# GPIO_SW.net
KiCad netlist of a schematic drawn in Altium Designer
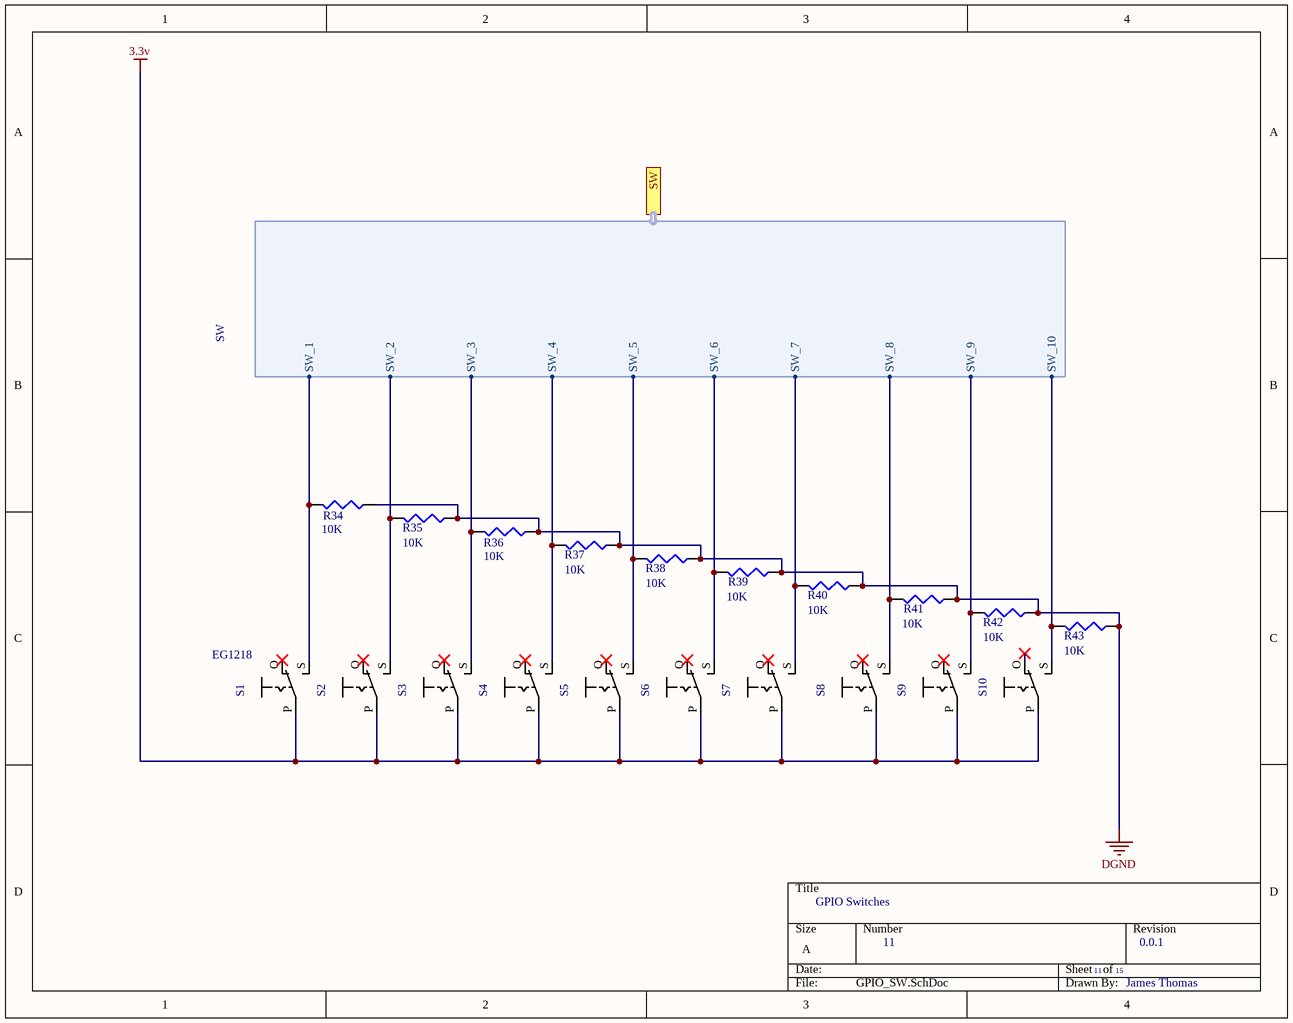
[diagram p0: GPIO_SW.SchDoc]

(export (version "E")
  (design (tool "Eeschema 10.0.6"))
  (components
    (comp (ref "R34")
      (value "10K")
      (footprint "J1-0603")
      (description "Resistor")
      (fields (field (name "Comment") "Res3") (field (name "PUBLISHER") "Altium Limited"))
      (libsource (lib "Miscellaneous Devices") (part "Res3"))
    )
    (comp (ref "R35")
      (value "10K")
      (footprint "J1-0603")
      (description "Resistor")
      (fields (field (name "Comment") "Res3") (field (name "PUBLISHER") "Altium Limited"))
      (libsource (lib "Miscellaneous Devices") (part "Res3"))
    )
    (comp (ref "R36")
      (value "10K")
      (footprint "J1-0603")
      (description "Resistor")
      (fields (field (name "Comment") "Res3") (field (name "PUBLISHER") "Altium Limited"))
      (libsource (lib "Miscellaneous Devices") (part "Res3"))
    )
    (comp (ref "R37")
      (value "10K")
      (footprint "J1-0603")
      (description "Resistor")
      (fields (field (name "Comment") "Res3") (field (name "PUBLISHER") "Altium Limited"))
      (libsource (lib "Miscellaneous Devices") (part "Res3"))
    )
    (comp (ref "R38")
      (value "10K")
      (footprint "J1-0603")
      (description "Resistor")
      (fields (field (name "Comment") "Res3") (field (name "PUBLISHER") "Altium Limited"))
      (libsource (lib "Miscellaneous Devices") (part "Res3"))
    )
    (comp (ref "R39")
      (value "10K")
      (footprint "J1-0603")
      (description "Resistor")
      (fields (field (name "Comment") "Res3") (field (name "PUBLISHER") "Altium Limited"))
      (libsource (lib "Miscellaneous Devices") (part "Res3"))
    )
    (comp (ref "R40")
      (value "10K")
      (footprint "J1-0603")
      (description "Resistor")
      (fields (field (name "Comment") "Res3") (field (name "PUBLISHER") "Altium Limited"))
      (libsource (lib "Miscellaneous Devices") (part "Res3"))
    )
    (comp (ref "R41")
      (value "10K")
      (footprint "J1-0603")
      (description "Resistor")
      (fields (field (name "Comment") "Res3") (field (name "PUBLISHER") "Altium Limited"))
      (libsource (lib "Miscellaneous Devices") (part "Res3"))
    )
    (comp (ref "R42")
      (value "10K")
      (footprint "J1-0603")
      (description "Resistor")
      (fields (field (name "Comment") "Res3") (field (name "PUBLISHER") "Altium Limited"))
      (libsource (lib "Miscellaneous Devices") (part "Res3"))
    )
    (comp (ref "R43")
      (value "10K")
      (footprint "J1-0603")
      (description "Resistor")
      (fields (field (name "Comment") "Res3") (field (name "PUBLISHER") "Altium Limited"))
      (libsource (lib "Miscellaneous Devices") (part "Res3"))
    )
    (comp (ref "S1")
      (value "EG1218")
      (footprint "*EG1218_EG1218(Primary)")
      (description "Slide Switch SPDT Through Hole")
      (fields (field (name "MF") "E-Switch") (field (name "DIGI-KEY_PART_NUMBER") "EG1903-ND"))
      (libsource (lib "Components") (part "EG1218"))
    )
    (comp (ref "S2")
      (value "EG1218")
      (footprint "*EG1218_EG1218(Primary)")
      (description "Slide Switch SPDT Through Hole")
      (fields (field (name "MF") "E-Switch") (field (name "DIGI-KEY_PART_NUMBER") "EG1903-ND"))
      (libsource (lib "Components") (part "EG1218"))
    )
    (comp (ref "S3")
      (value "EG1218")
      (footprint "*EG1218_EG1218(Primary)")
      (description "Slide Switch SPDT Through Hole")
      (fields (field (name "MF") "E-Switch") (field (name "DIGI-KEY_PART_NUMBER") "EG1903-ND"))
      (libsource (lib "Components") (part "EG1218"))
    )
    (comp (ref "S4")
      (value "EG1218")
      (footprint "*EG1218_EG1218(Primary)")
      (description "Slide Switch SPDT Through Hole")
      (fields (field (name "MF") "E-Switch") (field (name "DIGI-KEY_PART_NUMBER") "EG1903-ND"))
      (libsource (lib "Components") (part "EG1218"))
    )
    (comp (ref "S5")
      (value "EG1218")
      (footprint "*EG1218_EG1218(Primary)")
      (description "Slide Switch SPDT Through Hole")
      (fields (field (name "MF") "E-Switch") (field (name "DIGI-KEY_PART_NUMBER") "EG1903-ND"))
      (libsource (lib "Components") (part "EG1218"))
    )
    (comp (ref "S6")
      (value "EG1218")
      (footprint "*EG1218_EG1218(Primary)")
      (description "Slide Switch SPDT Through Hole")
      (fields (field (name "MF") "E-Switch") (field (name "DIGI-KEY_PART_NUMBER") "EG1903-ND"))
      (libsource (lib "Components") (part "EG1218"))
    )
    (comp (ref "S7")
      (value "EG1218")
      (footprint "*EG1218_EG1218(Primary)")
      (description "Slide Switch SPDT Through Hole")
      (fields (field (name "MF") "E-Switch") (field (name "DIGI-KEY_PART_NUMBER") "EG1903-ND"))
      (libsource (lib "Components") (part "EG1218"))
    )
    (comp (ref "S8")
      (value "EG1218")
      (footprint "*EG1218_EG1218(Primary)")
      (description "Slide Switch SPDT Through Hole")
      (fields (field (name "MF") "E-Switch") (field (name "DIGI-KEY_PART_NUMBER") "EG1903-ND"))
      (libsource (lib "Components") (part "EG1218"))
    )
    (comp (ref "S9")
      (value "EG1218")
      (footprint "*EG1218_EG1218(Primary)")
      (description "Slide Switch SPDT Through Hole")
      (fields (field (name "MF") "E-Switch") (field (name "DIGI-KEY_PART_NUMBER") "EG1903-ND"))
      (libsource (lib "Components") (part "EG1218"))
    )
    (comp (ref "S10")
      (value "EG1218")
      (footprint "*EG1218_EG1218(Primary)")
      (description "Slide Switch SPDT Through Hole")
      (fields (field (name "MF") "E-Switch") (field (name "DIGI-KEY_PART_NUMBER") "EG1903-ND"))
      (libsource (lib "Components") (part "EG1218"))
    )
  )
  (nets
    (net (code "3") (name "3.3v") (class "Default")
      (node (ref "S1") (pin "P") (pinfunction "P_P") (pintype "passive"))
      (node (ref "S10") (pin "P") (pinfunction "P_P") (pintype "passive"))
      (node (ref "S2") (pin "P") (pinfunction "P_P") (pintype "passive"))
      (node (ref "S3") (pin "P") (pinfunction "P_P") (pintype "passive"))
      (node (ref "S4") (pin "P") (pinfunction "P_P") (pintype "passive"))
      (node (ref "S5") (pin "P") (pinfunction "P_P") (pintype "passive"))
      (node (ref "S6") (pin "P") (pinfunction "P_P") (pintype "passive"))
      (node (ref "S7") (pin "P") (pinfunction "P_P") (pintype "passive"))
      (node (ref "S8") (pin "P") (pinfunction "P_P") (pintype "passive"))
      (node (ref "S9") (pin "P") (pinfunction "P_P") (pintype "passive"))
    )
    (net (code "4") (name "DGND") (class "Default")
      (node (ref "R34") (pin "1") (pinfunction "1_1") (pintype "passive"))
      (node (ref "R35") (pin "1") (pinfunction "1_1") (pintype "passive"))
      (node (ref "R36") (pin "1") (pinfunction "1_1") (pintype "passive"))
      (node (ref "R37") (pin "1") (pinfunction "1_1") (pintype "passive"))
      (node (ref "R38") (pin "1") (pinfunction "1_1") (pintype "passive"))
      (node (ref "R39") (pin "1") (pinfunction "1_1") (pintype "passive"))
      (node (ref "R40") (pin "1") (pinfunction "1_1") (pintype "passive"))
      (node (ref "R41") (pin "1") (pinfunction "1_1") (pintype "passive"))
      (node (ref "R42") (pin "1") (pinfunction "1_1") (pintype "passive"))
      (node (ref "R43") (pin "1") (pinfunction "1_1") (pintype "passive"))
    )
    (net (code "5") (name "Net-(R34-Pad2)") (class "Default")
      (node (ref "R34") (pin "2") (pinfunction "2_2") (pintype "passive"))
      (node (ref "S1") (pin "S") (pinfunction "S_S") (pintype "passive"))
    )
    (net (code "6") (name "Net-(R35-Pad2)") (class "Default")
      (node (ref "R35") (pin "2") (pinfunction "2_2") (pintype "passive"))
      (node (ref "S2") (pin "S") (pinfunction "S_S") (pintype "passive"))
    )
    (net (code "7") (name "Net-(R36-Pad2)") (class "Default")
      (node (ref "R36") (pin "2") (pinfunction "2_2") (pintype "passive"))
      (node (ref "S3") (pin "S") (pinfunction "S_S") (pintype "passive"))
    )
    (net (code "8") (name "Net-(R37-Pad2)") (class "Default")
      (node (ref "R37") (pin "2") (pinfunction "2_2") (pintype "passive"))
      (node (ref "S4") (pin "S") (pinfunction "S_S") (pintype "passive"))
    )
    (net (code "9") (name "Net-(R38-Pad2)") (class "Default")
      (node (ref "R38") (pin "2") (pinfunction "2_2") (pintype "passive"))
      (node (ref "S5") (pin "S") (pinfunction "S_S") (pintype "passive"))
    )
    (net (code "10") (name "Net-(R39-Pad2)") (class "Default")
      (node (ref "R39") (pin "2") (pinfunction "2_2") (pintype "passive"))
      (node (ref "S6") (pin "S") (pinfunction "S_S") (pintype "passive"))
    )
    (net (code "11") (name "Net-(R40-Pad2)") (class "Default")
      (node (ref "R40") (pin "2") (pinfunction "2_2") (pintype "passive"))
      (node (ref "S7") (pin "S") (pinfunction "S_S") (pintype "passive"))
    )
    (net (code "12") (name "Net-(R41-Pad2)") (class "Default")
      (node (ref "R41") (pin "2") (pinfunction "2_2") (pintype "passive"))
      (node (ref "S8") (pin "S") (pinfunction "S_S") (pintype "passive"))
    )
    (net (code "13") (name "Net-(R42-Pad2)") (class "Default")
      (node (ref "R42") (pin "2") (pinfunction "2_2") (pintype "passive"))
      (node (ref "S9") (pin "S") (pinfunction "S_S") (pintype "passive"))
    )
    (net (code "14") (name "Net-(R43-Pad2)") (class "Default")
      (node (ref "R43") (pin "2") (pinfunction "2_2") (pintype "passive"))
      (node (ref "S10") (pin "S") (pinfunction "S_S") (pintype "passive"))
    )
    (net (code "15") (name "unconnected-(S1-PadO)") (class "Default")
      (node (ref "S1") (pin "O") (pinfunction "O_O") (pintype "passive+no_connect"))
    )
    (net (code "16") (name "unconnected-(S2-PadO)") (class "Default")
      (node (ref "S2") (pin "O") (pinfunction "O_O") (pintype "passive+no_connect"))
    )
    (net (code "17") (name "unconnected-(S3-PadO)") (class "Default")
      (node (ref "S3") (pin "O") (pinfunction "O_O") (pintype "passive+no_connect"))
    )
    (net (code "18") (name "unconnected-(S4-PadO)") (class "Default")
      (node (ref "S4") (pin "O") (pinfunction "O_O") (pintype "passive+no_connect"))
    )
    (net (code "19") (name "unconnected-(S5-PadO)") (class "Default")
      (node (ref "S5") (pin "O") (pinfunction "O_O") (pintype "passive+no_connect"))
    )
    (net (code "20") (name "unconnected-(S6-PadO)") (class "Default")
      (node (ref "S6") (pin "O") (pinfunction "O_O") (pintype "passive+no_connect"))
    )
    (net (code "21") (name "unconnected-(S7-PadO)") (class "Default")
      (node (ref "S7") (pin "O") (pinfunction "O_O") (pintype "passive+no_connect"))
    )
    (net (code "22") (name "unconnected-(S8-PadO)") (class "Default")
      (node (ref "S8") (pin "O") (pinfunction "O_O") (pintype "passive+no_connect"))
    )
    (net (code "23") (name "unconnected-(S9-PadO)") (class "Default")
      (node (ref "S9") (pin "O") (pinfunction "O_O") (pintype "passive+no_connect"))
    )
    (net (code "24") (name "unconnected-(S10-PadO)") (class "Default")
      (node (ref "S10") (pin "O") (pinfunction "O_O") (pintype "passive+no_connect"))
    )
  )
)
